# shield.net
KiCad netlist of a schematic drawn in EAGLE
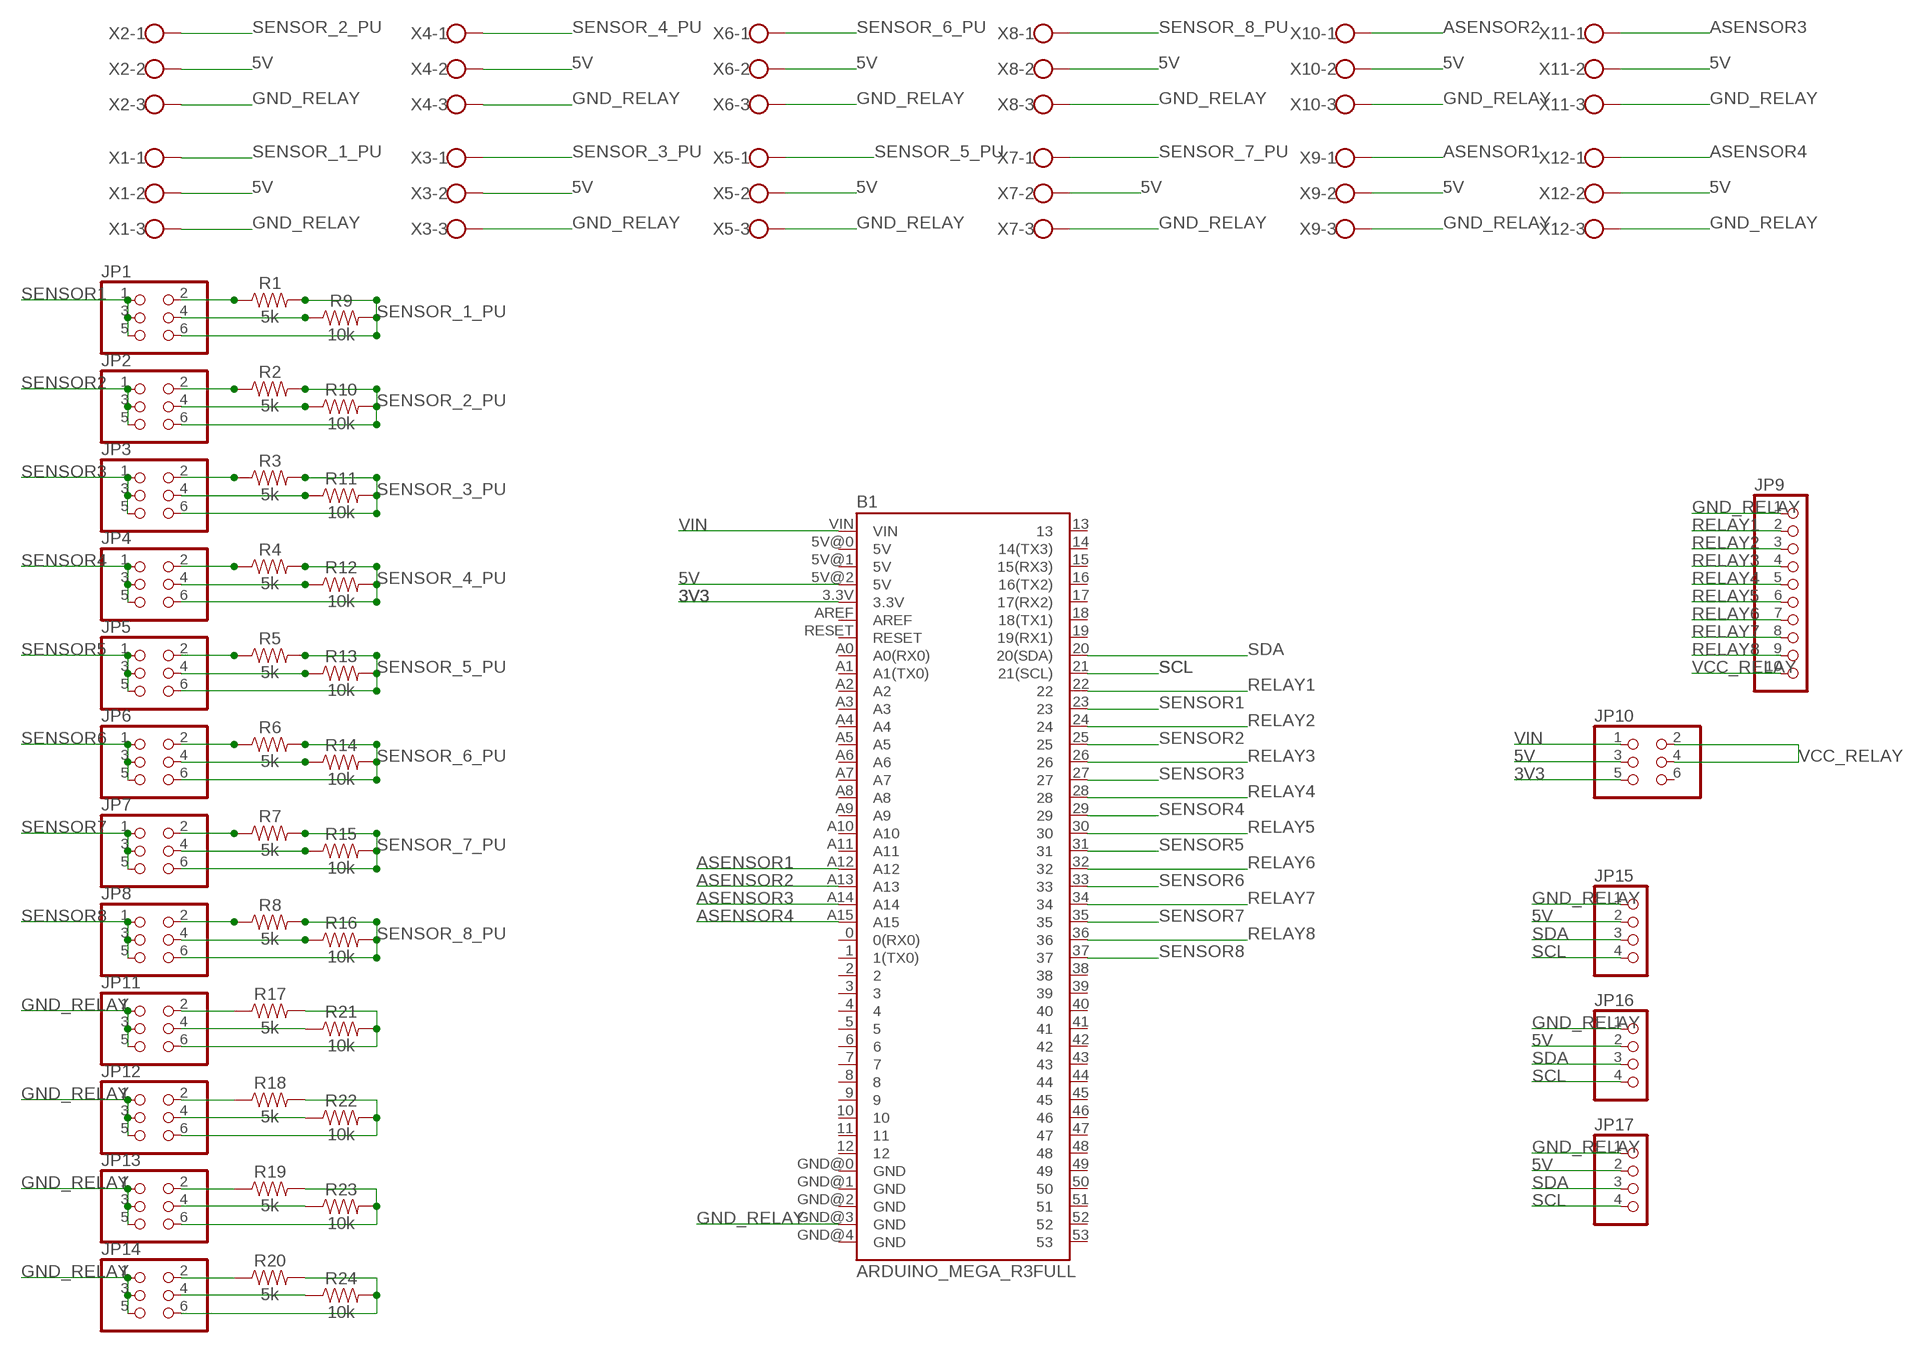
[diagram p0: schematic, sheet 1]

(export (version "E")
  (design (tool "Eeschema 10.0.6"))
  (components
    (comp (ref "B1")
      (value "ARDUINO_MEGA_R3FULL")
      (footprint "eagle-import:ARDUINO_MEGA")
      (libsource (lib "eagle-import") (part "ARDUINO_MEGA_R3FULL"))
    )
    (comp (ref "JP1")
      (value "PINHD-2X3")
      (footprint "eagle-import:2X03")
      (libsource (lib "eagle-import") (part "PINHD-2X3"))
    )
    (comp (ref "JP2")
      (value "PINHD-2X3")
      (footprint "eagle-import:2X03")
      (libsource (lib "eagle-import") (part "PINHD-2X3"))
    )
    (comp (ref "JP3")
      (value "PINHD-2X3")
      (footprint "eagle-import:2X03")
      (libsource (lib "eagle-import") (part "PINHD-2X3"))
    )
    (comp (ref "JP4")
      (value "PINHD-2X3")
      (footprint "eagle-import:2X03")
      (libsource (lib "eagle-import") (part "PINHD-2X3"))
    )
    (comp (ref "JP5")
      (value "PINHD-2X3")
      (footprint "eagle-import:2X03")
      (libsource (lib "eagle-import") (part "PINHD-2X3"))
    )
    (comp (ref "JP6")
      (value "PINHD-2X3")
      (footprint "eagle-import:2X03")
      (libsource (lib "eagle-import") (part "PINHD-2X3"))
    )
    (comp (ref "JP7")
      (value "PINHD-2X3")
      (footprint "eagle-import:2X03")
      (libsource (lib "eagle-import") (part "PINHD-2X3"))
    )
    (comp (ref "JP8")
      (value "PINHD-2X3")
      (footprint "eagle-import:2X03")
      (libsource (lib "eagle-import") (part "PINHD-2X3"))
    )
    (comp (ref "JP9")
      (value "PINHD-1X10")
      (footprint "eagle-import:1X10")
      (libsource (lib "eagle-import") (part "PINHD-1X10"))
    )
    (comp (ref "JP10")
      (value "PINHD-2X3")
      (footprint "eagle-import:2X03")
      (libsource (lib "eagle-import") (part "PINHD-2X3"))
    )
    (comp (ref "JP11")
      (value "PINHD-2X3")
      (footprint "eagle-import:2X03")
      (libsource (lib "eagle-import") (part "PINHD-2X3"))
    )
    (comp (ref "JP12")
      (value "PINHD-2X3")
      (footprint "eagle-import:2X03")
      (libsource (lib "eagle-import") (part "PINHD-2X3"))
    )
    (comp (ref "JP13")
      (value "PINHD-2X3")
      (footprint "eagle-import:2X03")
      (libsource (lib "eagle-import") (part "PINHD-2X3"))
    )
    (comp (ref "JP14")
      (value "PINHD-2X3")
      (footprint "eagle-import:2X03")
      (libsource (lib "eagle-import") (part "PINHD-2X3"))
    )
    (comp (ref "JP15")
      (value "PINHD-1X4")
      (footprint "eagle-import:1X04")
      (libsource (lib "eagle-import") (part "PINHD-1X4"))
    )
    (comp (ref "JP16")
      (value "PINHD-1X4")
      (footprint "eagle-import:1X04")
      (libsource (lib "eagle-import") (part "PINHD-1X4"))
    )
    (comp (ref "JP17")
      (value "PINHD-1X4")
      (footprint "eagle-import:1X04")
      (libsource (lib "eagle-import") (part "PINHD-1X4"))
    )
    (comp (ref "R1")
      (value "5k")
      (footprint "eagle-import:AXIAL-0.3")
      (libsource (lib "eagle-import") (part "10KOHM-HORIZ-1/4W-1%"))
    )
    (comp (ref "R2")
      (value "5k")
      (footprint "eagle-import:AXIAL-0.3")
      (libsource (lib "eagle-import") (part "10KOHM-HORIZ-1/4W-1%"))
    )
    (comp (ref "R3")
      (value "5k")
      (footprint "eagle-import:AXIAL-0.3")
      (libsource (lib "eagle-import") (part "10KOHM-HORIZ-1/4W-1%"))
    )
    (comp (ref "R4")
      (value "5k")
      (footprint "eagle-import:AXIAL-0.3")
      (libsource (lib "eagle-import") (part "10KOHM-HORIZ-1/4W-1%"))
    )
    (comp (ref "R5")
      (value "5k")
      (footprint "eagle-import:AXIAL-0.3")
      (libsource (lib "eagle-import") (part "10KOHM-HORIZ-1/4W-1%"))
    )
    (comp (ref "R6")
      (value "5k")
      (footprint "eagle-import:AXIAL-0.3")
      (libsource (lib "eagle-import") (part "10KOHM-HORIZ-1/4W-1%"))
    )
    (comp (ref "R7")
      (value "5k")
      (footprint "eagle-import:AXIAL-0.3")
      (libsource (lib "eagle-import") (part "10KOHM-HORIZ-1/4W-1%"))
    )
    (comp (ref "R8")
      (value "5k")
      (footprint "eagle-import:AXIAL-0.3")
      (libsource (lib "eagle-import") (part "10KOHM-HORIZ-1/4W-1%"))
    )
    (comp (ref "R9")
      (value "10k")
      (footprint "eagle-import:AXIAL-0.3")
      (libsource (lib "eagle-import") (part "10KOHM-HORIZ-1/4W-1%"))
    )
    (comp (ref "R10")
      (value "10k")
      (footprint "eagle-import:AXIAL-0.3")
      (libsource (lib "eagle-import") (part "10KOHM-HORIZ-1/4W-1%"))
    )
    (comp (ref "R11")
      (value "10k")
      (footprint "eagle-import:AXIAL-0.3")
      (libsource (lib "eagle-import") (part "10KOHM-HORIZ-1/4W-1%"))
    )
    (comp (ref "R12")
      (value "10k")
      (footprint "eagle-import:AXIAL-0.3")
      (libsource (lib "eagle-import") (part "10KOHM-HORIZ-1/4W-1%"))
    )
    (comp (ref "R13")
      (value "10k")
      (footprint "eagle-import:AXIAL-0.3")
      (libsource (lib "eagle-import") (part "10KOHM-HORIZ-1/4W-1%"))
    )
    (comp (ref "R14")
      (value "10k")
      (footprint "eagle-import:AXIAL-0.3")
      (libsource (lib "eagle-import") (part "10KOHM-HORIZ-1/4W-1%"))
    )
    (comp (ref "R15")
      (value "10k")
      (footprint "eagle-import:AXIAL-0.3")
      (libsource (lib "eagle-import") (part "10KOHM-HORIZ-1/4W-1%"))
    )
    (comp (ref "R16")
      (value "10k")
      (footprint "eagle-import:AXIAL-0.3")
      (libsource (lib "eagle-import") (part "10KOHM-HORIZ-1/4W-1%"))
    )
    (comp (ref "R17")
      (value "5k")
      (footprint "eagle-import:AXIAL-0.3")
      (libsource (lib "eagle-import") (part "10KOHM-HORIZ-1/4W-1%"))
    )
    (comp (ref "R18")
      (value "5k")
      (footprint "eagle-import:AXIAL-0.3")
      (libsource (lib "eagle-import") (part "10KOHM-HORIZ-1/4W-1%"))
    )
    (comp (ref "R19")
      (value "5k")
      (footprint "eagle-import:AXIAL-0.3")
      (libsource (lib "eagle-import") (part "10KOHM-HORIZ-1/4W-1%"))
    )
    (comp (ref "R20")
      (value "5k")
      (footprint "eagle-import:AXIAL-0.3")
      (libsource (lib "eagle-import") (part "10KOHM-HORIZ-1/4W-1%"))
    )
    (comp (ref "R21")
      (value "10k")
      (footprint "eagle-import:AXIAL-0.3")
      (libsource (lib "eagle-import") (part "10KOHM-HORIZ-1/4W-1%"))
    )
    (comp (ref "R22")
      (value "10k")
      (footprint "eagle-import:AXIAL-0.3")
      (libsource (lib "eagle-import") (part "10KOHM-HORIZ-1/4W-1%"))
    )
    (comp (ref "R23")
      (value "10k")
      (footprint "eagle-import:AXIAL-0.3")
      (libsource (lib "eagle-import") (part "10KOHM-HORIZ-1/4W-1%"))
    )
    (comp (ref "R24")
      (value "10k")
      (footprint "eagle-import:AXIAL-0.3")
      (libsource (lib "eagle-import") (part "10KOHM-HORIZ-1/4W-1%"))
    )
    (comp (ref "X1")
      (value "W237-103")
      (footprint "eagle-import:W237-103")
      (fields (field (name "MPN") "237-103"))
      (libsource (lib "eagle-import") (part "W237-103"))
    )
    (comp (ref "X2")
      (value "W237-103")
      (footprint "eagle-import:W237-103")
      (fields (field (name "MPN") "237-103"))
      (libsource (lib "eagle-import") (part "W237-103"))
    )
    (comp (ref "X3")
      (value "W237-103")
      (footprint "eagle-import:W237-103")
      (fields (field (name "MPN") "237-103"))
      (libsource (lib "eagle-import") (part "W237-103"))
    )
    (comp (ref "X4")
      (value "W237-103")
      (footprint "eagle-import:W237-103")
      (fields (field (name "MPN") "237-103"))
      (libsource (lib "eagle-import") (part "W237-103"))
    )
    (comp (ref "X5")
      (value "W237-103")
      (footprint "eagle-import:W237-103")
      (fields (field (name "MPN") "237-103"))
      (libsource (lib "eagle-import") (part "W237-103"))
    )
    (comp (ref "X6")
      (value "W237-103")
      (footprint "eagle-import:W237-103")
      (fields (field (name "MPN") "237-103"))
      (libsource (lib "eagle-import") (part "W237-103"))
    )
    (comp (ref "X7")
      (value "W237-103")
      (footprint "eagle-import:W237-103")
      (fields (field (name "MPN") "237-103"))
      (libsource (lib "eagle-import") (part "W237-103"))
    )
    (comp (ref "X8")
      (value "W237-103")
      (footprint "eagle-import:W237-103")
      (fields (field (name "MPN") "237-103"))
      (libsource (lib "eagle-import") (part "W237-103"))
    )
    (comp (ref "X9")
      (value "W237-103")
      (footprint "eagle-import:W237-103")
      (fields (field (name "MPN") "237-103"))
      (libsource (lib "eagle-import") (part "W237-103"))
    )
    (comp (ref "X10")
      (value "W237-103")
      (footprint "eagle-import:W237-103")
      (fields (field (name "MPN") "237-103"))
      (libsource (lib "eagle-import") (part "W237-103"))
    )
    (comp (ref "X11")
      (value "W237-103")
      (footprint "eagle-import:W237-103")
      (fields (field (name "MPN") "237-103"))
      (libsource (lib "eagle-import") (part "W237-103"))
    )
    (comp (ref "X12")
      (value "W237-103")
      (footprint "eagle-import:W237-103")
      (fields (field (name "MPN") "237-103"))
      (libsource (lib "eagle-import") (part "W237-103"))
    )
  )
  (nets
    (net (code "1") (name "/3V3") (class "Default")
      (node (ref "B1") (pin "3.3V") (pinfunction "3.3V_3.3V") (pintype "bidirectional"))
      (node (ref "JP10") (pin "5") (pinfunction "5_5") (pintype "passive"))
    )
    (net (code "2") (name "/5V") (class "Default")
      (node (ref "B1") (pin "5V@2") (pinfunction "5V_5V@2") (pintype "bidirectional"))
      (node (ref "JP10") (pin "3") (pinfunction "3_3") (pintype "passive"))
      (node (ref "JP15") (pin "2") (pinfunction "2_2") (pintype "passive"))
      (node (ref "JP16") (pin "2") (pinfunction "2_2") (pintype "passive"))
      (node (ref "JP17") (pin "2") (pinfunction "2_2") (pintype "passive"))
      (node (ref "X1") (pin "2") (pinfunction "KL_2") (pintype "passive"))
      (node (ref "X10") (pin "2") (pinfunction "KL_2") (pintype "passive"))
      (node (ref "X11") (pin "2") (pinfunction "KL_2") (pintype "passive"))
      (node (ref "X12") (pin "2") (pinfunction "KL_2") (pintype "passive"))
      (node (ref "X2") (pin "2") (pinfunction "KL_2") (pintype "passive"))
      (node (ref "X3") (pin "2") (pinfunction "KL_2") (pintype "passive"))
      (node (ref "X4") (pin "2") (pinfunction "KL_2") (pintype "passive"))
      (node (ref "X5") (pin "2") (pinfunction "KL_2") (pintype "passive"))
      (node (ref "X6") (pin "2") (pinfunction "KL_2") (pintype "passive"))
      (node (ref "X7") (pin "2") (pinfunction "KL_2") (pintype "passive"))
      (node (ref "X8") (pin "2") (pinfunction "KL_2") (pintype "passive"))
      (node (ref "X9") (pin "2") (pinfunction "KL_2") (pintype "passive"))
    )
    (net (code "3") (name "/ASENSOR1") (class "Default")
      (node (ref "B1") (pin "A12") (pinfunction "A12_A12") (pintype "bidirectional"))
      (node (ref "X9") (pin "1") (pinfunction "KL_1") (pintype "passive"))
    )
    (net (code "4") (name "/ASENSOR2") (class "Default")
      (node (ref "B1") (pin "A13") (pinfunction "A13_A13") (pintype "bidirectional"))
      (node (ref "X10") (pin "1") (pinfunction "KL_1") (pintype "passive"))
    )
    (net (code "5") (name "/ASENSOR3") (class "Default")
      (node (ref "B1") (pin "A14") (pinfunction "A14_A14") (pintype "bidirectional"))
      (node (ref "X11") (pin "1") (pinfunction "KL_1") (pintype "passive"))
    )
    (net (code "6") (name "/ASENSOR4") (class "Default")
      (node (ref "B1") (pin "A15") (pinfunction "A15_A15") (pintype "bidirectional"))
      (node (ref "X12") (pin "1") (pinfunction "KL_1") (pintype "passive"))
    )
    (net (code "7") (name "/GND_RELAY") (class "Default")
      (node (ref "B1") (pin "GND@3") (pinfunction "GND_GND@3") (pintype "bidirectional"))
      (node (ref "JP11") (pin "1") (pinfunction "1_1") (pintype "passive"))
      (node (ref "JP11") (pin "3") (pinfunction "3_3") (pintype "passive"))
      (node (ref "JP11") (pin "5") (pinfunction "5_5") (pintype "passive"))
      (node (ref "JP12") (pin "1") (pinfunction "1_1") (pintype "passive"))
      (node (ref "JP12") (pin "3") (pinfunction "3_3") (pintype "passive"))
      (node (ref "JP12") (pin "5") (pinfunction "5_5") (pintype "passive"))
      (node (ref "JP13") (pin "1") (pinfunction "1_1") (pintype "passive"))
      (node (ref "JP13") (pin "3") (pinfunction "3_3") (pintype "passive"))
      (node (ref "JP13") (pin "5") (pinfunction "5_5") (pintype "passive"))
      (node (ref "JP14") (pin "1") (pinfunction "1_1") (pintype "passive"))
      (node (ref "JP14") (pin "3") (pinfunction "3_3") (pintype "passive"))
      (node (ref "JP14") (pin "5") (pinfunction "5_5") (pintype "passive"))
      (node (ref "JP15") (pin "1") (pinfunction "1_1") (pintype "passive"))
      (node (ref "JP16") (pin "1") (pinfunction "1_1") (pintype "passive"))
      (node (ref "JP17") (pin "1") (pinfunction "1_1") (pintype "passive"))
      (node (ref "JP9") (pin "1") (pinfunction "1_1") (pintype "passive"))
      (node (ref "X1") (pin "3") (pinfunction "KL_3") (pintype "passive"))
      (node (ref "X10") (pin "3") (pinfunction "KL_3") (pintype "passive"))
      (node (ref "X11") (pin "3") (pinfunction "KL_3") (pintype "passive"))
      (node (ref "X12") (pin "3") (pinfunction "KL_3") (pintype "passive"))
      (node (ref "X2") (pin "3") (pinfunction "KL_3") (pintype "passive"))
      (node (ref "X3") (pin "3") (pinfunction "KL_3") (pintype "passive"))
      (node (ref "X4") (pin "3") (pinfunction "KL_3") (pintype "passive"))
      (node (ref "X5") (pin "3") (pinfunction "KL_3") (pintype "passive"))
      (node (ref "X6") (pin "3") (pinfunction "KL_3") (pintype "passive"))
      (node (ref "X7") (pin "3") (pinfunction "KL_3") (pintype "passive"))
      (node (ref "X8") (pin "3") (pinfunction "KL_3") (pintype "passive"))
      (node (ref "X9") (pin "3") (pinfunction "KL_3") (pintype "passive"))
    )
    (net (code "8") (name "/RELAY1") (class "Default")
      (node (ref "B1") (pin "22") (pinfunction "22_22") (pintype "bidirectional"))
      (node (ref "JP9") (pin "2") (pinfunction "2_2") (pintype "passive"))
    )
    (net (code "9") (name "/RELAY2") (class "Default")
      (node (ref "B1") (pin "24") (pinfunction "24_24") (pintype "bidirectional"))
      (node (ref "JP9") (pin "3") (pinfunction "3_3") (pintype "passive"))
    )
    (net (code "10") (name "/RELAY3") (class "Default")
      (node (ref "B1") (pin "26") (pinfunction "26_26") (pintype "bidirectional"))
      (node (ref "JP9") (pin "4") (pinfunction "4_4") (pintype "passive"))
    )
    (net (code "11") (name "/RELAY4") (class "Default")
      (node (ref "B1") (pin "28") (pinfunction "28_28") (pintype "bidirectional"))
      (node (ref "JP9") (pin "5") (pinfunction "5_5") (pintype "passive"))
    )
    (net (code "12") (name "/RELAY5") (class "Default")
      (node (ref "B1") (pin "30") (pinfunction "30_30") (pintype "bidirectional"))
      (node (ref "JP9") (pin "6") (pinfunction "6_6") (pintype "passive"))
    )
    (net (code "13") (name "/RELAY6") (class "Default")
      (node (ref "B1") (pin "32") (pinfunction "32_32") (pintype "bidirectional"))
      (node (ref "JP9") (pin "7") (pinfunction "7_7") (pintype "passive"))
    )
    (net (code "14") (name "/RELAY7") (class "Default")
      (node (ref "B1") (pin "34") (pinfunction "34_34") (pintype "bidirectional"))
      (node (ref "JP9") (pin "8") (pinfunction "8_8") (pintype "passive"))
    )
    (net (code "15") (name "/RELAY8") (class "Default")
      (node (ref "B1") (pin "36") (pinfunction "36_36") (pintype "bidirectional"))
      (node (ref "JP9") (pin "9") (pinfunction "9_9") (pintype "passive"))
    )
    (net (code "16") (name "/SCL") (class "Default")
      (node (ref "B1") (pin "21") (pinfunction "21(SCL)_21") (pintype "bidirectional"))
      (node (ref "JP15") (pin "4") (pinfunction "4_4") (pintype "passive"))
      (node (ref "JP16") (pin "4") (pinfunction "4_4") (pintype "passive"))
      (node (ref "JP17") (pin "4") (pinfunction "4_4") (pintype "passive"))
    )
    (net (code "17") (name "/SDA") (class "Default")
      (node (ref "B1") (pin "20") (pinfunction "20(SDA)_20") (pintype "bidirectional"))
      (node (ref "JP15") (pin "3") (pinfunction "3_3") (pintype "passive"))
      (node (ref "JP16") (pin "3") (pinfunction "3_3") (pintype "passive"))
      (node (ref "JP17") (pin "3") (pinfunction "3_3") (pintype "passive"))
    )
    (net (code "18") (name "/SENSOR1") (class "Default")
      (node (ref "B1") (pin "23") (pinfunction "23_23") (pintype "bidirectional"))
      (node (ref "JP1") (pin "1") (pinfunction "1_1") (pintype "passive"))
      (node (ref "JP1") (pin "3") (pinfunction "3_3") (pintype "passive"))
      (node (ref "JP1") (pin "5") (pinfunction "5_5") (pintype "passive"))
    )
    (net (code "19") (name "/SENSOR2") (class "Default")
      (node (ref "B1") (pin "25") (pinfunction "25_25") (pintype "bidirectional"))
      (node (ref "JP2") (pin "1") (pinfunction "1_1") (pintype "passive"))
      (node (ref "JP2") (pin "3") (pinfunction "3_3") (pintype "passive"))
      (node (ref "JP2") (pin "5") (pinfunction "5_5") (pintype "passive"))
    )
    (net (code "20") (name "/SENSOR3") (class "Default")
      (node (ref "B1") (pin "27") (pinfunction "27_27") (pintype "bidirectional"))
      (node (ref "JP3") (pin "1") (pinfunction "1_1") (pintype "passive"))
      (node (ref "JP3") (pin "3") (pinfunction "3_3") (pintype "passive"))
      (node (ref "JP3") (pin "5") (pinfunction "5_5") (pintype "passive"))
    )
    (net (code "21") (name "/SENSOR4") (class "Default")
      (node (ref "B1") (pin "29") (pinfunction "29_29") (pintype "bidirectional"))
      (node (ref "JP4") (pin "1") (pinfunction "1_1") (pintype "passive"))
      (node (ref "JP4") (pin "3") (pinfunction "3_3") (pintype "passive"))
      (node (ref "JP4") (pin "5") (pinfunction "5_5") (pintype "passive"))
    )
    (net (code "22") (name "/SENSOR5") (class "Default")
      (node (ref "B1") (pin "31") (pinfunction "31_31") (pintype "bidirectional"))
      (node (ref "JP5") (pin "1") (pinfunction "1_1") (pintype "passive"))
      (node (ref "JP5") (pin "3") (pinfunction "3_3") (pintype "passive"))
      (node (ref "JP5") (pin "5") (pinfunction "5_5") (pintype "passive"))
    )
    (net (code "23") (name "/SENSOR6") (class "Default")
      (node (ref "B1") (pin "33") (pinfunction "33_33") (pintype "bidirectional"))
      (node (ref "JP6") (pin "1") (pinfunction "1_1") (pintype "passive"))
      (node (ref "JP6") (pin "3") (pinfunction "3_3") (pintype "passive"))
      (node (ref "JP6") (pin "5") (pinfunction "5_5") (pintype "passive"))
    )
    (net (code "24") (name "/SENSOR7") (class "Default")
      (node (ref "B1") (pin "35") (pinfunction "35_35") (pintype "bidirectional"))
      (node (ref "JP7") (pin "1") (pinfunction "1_1") (pintype "passive"))
      (node (ref "JP7") (pin "3") (pinfunction "3_3") (pintype "passive"))
      (node (ref "JP7") (pin "5") (pinfunction "5_5") (pintype "passive"))
    )
    (net (code "25") (name "/SENSOR8") (class "Default")
      (node (ref "B1") (pin "37") (pinfunction "37_37") (pintype "bidirectional"))
      (node (ref "JP8") (pin "1") (pinfunction "1_1") (pintype "passive"))
      (node (ref "JP8") (pin "3") (pinfunction "3_3") (pintype "passive"))
      (node (ref "JP8") (pin "5") (pinfunction "5_5") (pintype "passive"))
    )
    (net (code "26") (name "/SENSOR_1_PU") (class "Default")
      (node (ref "JP1") (pin "6") (pinfunction "6_6") (pintype "passive"))
      (node (ref "R1") (pin "P$2") (pinfunction "2_P$2") (pintype "passive"))
      (node (ref "R9") (pin "P$2") (pinfunction "2_P$2") (pintype "passive"))
      (node (ref "X1") (pin "1") (pinfunction "KL_1") (pintype "passive"))
    )
    (net (code "27") (name "/SENSOR_2_PU") (class "Default")
      (node (ref "JP2") (pin "6") (pinfunction "6_6") (pintype "passive"))
      (node (ref "R10") (pin "P$2") (pinfunction "2_P$2") (pintype "passive"))
      (node (ref "R2") (pin "P$2") (pinfunction "2_P$2") (pintype "passive"))
      (node (ref "X2") (pin "1") (pinfunction "KL_1") (pintype "passive"))
    )
    (net (code "28") (name "/SENSOR_3_PU") (class "Default")
      (node (ref "JP3") (pin "6") (pinfunction "6_6") (pintype "passive"))
      (node (ref "R11") (pin "P$2") (pinfunction "2_P$2") (pintype "passive"))
      (node (ref "R3") (pin "P$2") (pinfunction "2_P$2") (pintype "passive"))
      (node (ref "X3") (pin "1") (pinfunction "KL_1") (pintype "passive"))
    )
    (net (code "29") (name "/SENSOR_4_PU") (class "Default")
      (node (ref "JP4") (pin "6") (pinfunction "6_6") (pintype "passive"))
      (node (ref "R12") (pin "P$2") (pinfunction "2_P$2") (pintype "passive"))
      (node (ref "R4") (pin "P$2") (pinfunction "2_P$2") (pintype "passive"))
      (node (ref "X4") (pin "1") (pinfunction "KL_1") (pintype "passive"))
    )
    (net (code "30") (name "/SENSOR_5_PU") (class "Default")
      (node (ref "JP5") (pin "6") (pinfunction "6_6") (pintype "passive"))
      (node (ref "R13") (pin "P$2") (pinfunction "2_P$2") (pintype "passive"))
      (node (ref "R5") (pin "P$2") (pinfunction "2_P$2") (pintype "passive"))
      (node (ref "X5") (pin "1") (pinfunction "KL_1") (pintype "passive"))
    )
    (net (code "31") (name "/SENSOR_6_PU") (class "Default")
      (node (ref "JP6") (pin "6") (pinfunction "6_6") (pintype "passive"))
      (node (ref "R14") (pin "P$2") (pinfunction "2_P$2") (pintype "passive"))
      (node (ref "R6") (pin "P$2") (pinfunction "2_P$2") (pintype "passive"))
      (node (ref "X6") (pin "1") (pinfunction "KL_1") (pintype "passive"))
    )
    (net (code "32") (name "/SENSOR_7_PU") (class "Default")
      (node (ref "JP7") (pin "6") (pinfunction "6_6") (pintype "passive"))
      (node (ref "R15") (pin "P$2") (pinfunction "2_P$2") (pintype "passive"))
      (node (ref "R7") (pin "P$2") (pinfunction "2_P$2") (pintype "passive"))
      (node (ref "X7") (pin "1") (pinfunction "KL_1") (pintype "passive"))
    )
    (net (code "33") (name "/SENSOR_8_PU") (class "Default")
      (node (ref "JP8") (pin "6") (pinfunction "6_6") (pintype "passive"))
      (node (ref "R16") (pin "P$2") (pinfunction "2_P$2") (pintype "passive"))
      (node (ref "R8") (pin "P$2") (pinfunction "2_P$2") (pintype "passive"))
      (node (ref "X8") (pin "1") (pinfunction "KL_1") (pintype "passive"))
    )
    (net (code "34") (name "/VCC_RELAY") (class "Default")
      (node (ref "JP10") (pin "2") (pinfunction "2_2") (pintype "passive"))
      (node (ref "JP10") (pin "4") (pinfunction "4_4") (pintype "passive"))
      (node (ref "JP9") (pin "10") (pinfunction "10_10") (pintype "passive"))
    )
    (net (code "35") (name "/VIN") (class "Default")
      (node (ref "B1") (pin "VIN") (pinfunction "VIN_VIN") (pintype "bidirectional"))
      (node (ref "JP10") (pin "1") (pinfunction "1_1") (pintype "passive"))
    )
    (net (code "36") (name "Net-(R1-1)") (class "Default")
      (node (ref "JP1") (pin "2") (pinfunction "2_2") (pintype "passive"))
      (node (ref "R1") (pin "P$1") (pinfunction "1_P$1") (pintype "passive"))
    )
    (net (code "37") (name "Net-(R2-1)") (class "Default")
      (node (ref "JP2") (pin "2") (pinfunction "2_2") (pintype "passive"))
      (node (ref "R2") (pin "P$1") (pinfunction "1_P$1") (pintype "passive"))
    )
    (net (code "38") (name "Net-(R3-1)") (class "Default")
      (node (ref "JP3") (pin "2") (pinfunction "2_2") (pintype "passive"))
      (node (ref "R3") (pin "P$1") (pinfunction "1_P$1") (pintype "passive"))
    )
    (net (code "39") (name "Net-(R4-1)") (class "Default")
      (node (ref "JP4") (pin "2") (pinfunction "2_2") (pintype "passive"))
      (node (ref "R4") (pin "P$1") (pinfunction "1_P$1") (pintype "passive"))
    )
    (net (code "40") (name "Net-(R5-1)") (class "Default")
      (node (ref "JP5") (pin "2") (pinfunction "2_2") (pintype "passive"))
      (node (ref "R5") (pin "P$1") (pinfunction "1_P$1") (pintype "passive"))
    )
    (net (code "41") (name "Net-(R6-1)") (class "Default")
      (node (ref "JP6") (pin "2") (pinfunction "2_2") (pintype "passive"))
      (node (ref "R6") (pin "P$1") (pinfunction "1_P$1") (pintype "passive"))
    )
    (net (code "42") (name "Net-(R7-1)") (class "Default")
      (node (ref "JP7") (pin "2") (pinfunction "2_2") (pintype "passive"))
      (node (ref "R7") (pin "P$1") (pinfunction "1_P$1") (pintype "passive"))
    )
    (net (code "43") (name "Net-(R8-1)") (class "Default")
      (node (ref "JP8") (pin "2") (pinfunction "2_2") (pintype "passive"))
      (node (ref "R8") (pin "P$1") (pinfunction "1_P$1") (pintype "passive"))
    )
    (net (code "44") (name "Net-(R9-1)") (class "Default")
      (node (ref "JP1") (pin "4") (pinfunction "4_4") (pintype "passive"))
      (node (ref "R9") (pin "P$1") (pinfunction "1_P$1") (pintype "passive"))
    )
    (net (code "45") (name "Net-(R10-1)") (class "Default")
      (node (ref "JP2") (pin "4") (pinfunction "4_4") (pintype "passive"))
      (node (ref "R10") (pin "P$1") (pinfunction "1_P$1") (pintype "passive"))
    )
    (net (code "46") (name "Net-(R11-1)") (class "Default")
      (node (ref "JP3") (pin "4") (pinfunction "4_4") (pintype "passive"))
      (node (ref "R11") (pin "P$1") (pinfunction "1_P$1") (pintype "passive"))
    )
    (net (code "47") (name "Net-(R12-1)") (class "Default")
      (node (ref "JP4") (pin "4") (pinfunction "4_4") (pintype "passive"))
      (node (ref "R12") (pin "P$1") (pinfunction "1_P$1") (pintype "passive"))
    )
    (net (code "48") (name "Net-(R13-1)") (class "Default")
      (node (ref "JP5") (pin "4") (pinfunction "4_4") (pintype "passive"))
      (node (ref "R13") (pin "P$1") (pinfunction "1_P$1") (pintype "passive"))
    )
    (net (code "49") (name "Net-(R14-1)") (class "Default")
      (node (ref "JP6") (pin "4") (pinfunction "4_4") (pintype "passive"))
      (node (ref "R14") (pin "P$1") (pinfunction "1_P$1") (pintype "passive"))
    )
    (net (code "50") (name "Net-(R15-1)") (class "Default")
      (node (ref "JP7") (pin "4") (pinfunction "4_4") (pintype "passive"))
      (node (ref "R15") (pin "P$1") (pinfunction "1_P$1") (pintype "passive"))
    )
    (net (code "51") (name "Net-(R16-1)") (class "Default")
      (node (ref "JP8") (pin "4") (pinfunction "4_4") (pintype "passive"))
      (node (ref "R16") (pin "P$1") (pinfunction "1_P$1") (pintype "passive"))
    )
    (net (code "52") (name "Net-(R17-1)") (class "Default")
      (node (ref "JP11") (pin "2") (pinfunction "2_2") (pintype "passive"))
      (node (ref "R17") (pin "P$1") (pinfunction "1_P$1") (pintype "passive"))
    )
    (net (code "53") (name "Net-(R17-2)") (class "Default")
      (node (ref "JP11") (pin "6") (pinfunction "6_6") (pintype "passive"))
      (node (ref "R17") (pin "P$2") (pinfunction "2_P$2") (pintype "passive"))
      (node (ref "R21") (pin "P$2") (pinfunction "2_P$2") (pintype "passive"))
    )
    (net (code "54") (name "Net-(R18-1)") (class "Default")
      (node (ref "JP12") (pin "2") (pinfunction "2_2") (pintype "passive"))
      (node (ref "R18") (pin "P$1") (pinfunction "1_P$1") (pintype "passive"))
    )
    (net (code "55") (name "Net-(R18-2)") (class "Default")
      (node (ref "JP12") (pin "6") (pinfunction "6_6") (pintype "passive"))
      (node (ref "R18") (pin "P$2") (pinfunction "2_P$2") (pintype "passive"))
      (node (ref "R22") (pin "P$2") (pinfunction "2_P$2") (pintype "passive"))
    )
    (net (code "56") (name "Net-(R19-1)") (class "Default")
      (node (ref "JP13") (pin "2") (pinfunction "2_2") (pintype "passive"))
      (node (ref "R19") (pin "P$1") (pinfunction "1_P$1") (pintype "passive"))
    )
    (net (code "57") (name "Net-(R19-2)") (class "Default")
      (node (ref "JP13") (pin "6") (pinfunction "6_6") (pintype "passive"))
      (node (ref "R19") (pin "P$2") (pinfunction "2_P$2") (pintype "passive"))
      (node (ref "R23") (pin "P$2") (pinfunction "2_P$2") (pintype "passive"))
    )
    (net (code "58") (name "Net-(R20-1)") (class "Default")
      (node (ref "JP14") (pin "2") (pinfunction "2_2") (pintype "passive"))
      (node (ref "R20") (pin "P$1") (pinfunction "1_P$1") (pintype "passive"))
    )
    (net (code "59") (name "Net-(R20-2)") (class "Default")
      (node (ref "JP14") (pin "6") (pinfunction "6_6") (pintype "passive"))
      (node (ref "R20") (pin "P$2") (pinfunction "2_P$2") (pintype "passive"))
      (node (ref "R24") (pin "P$2") (pinfunction "2_P$2") (pintype "passive"))
    )
    (net (code "60") (name "Net-(R21-1)") (class "Default")
      (node (ref "JP11") (pin "4") (pinfunction "4_4") (pintype "passive"))
      (node (ref "R21") (pin "P$1") (pinfunction "1_P$1") (pintype "passive"))
    )
    (net (code "61") (name "Net-(R22-1)") (class "Default")
      (node (ref "JP12") (pin "4") (pinfunction "4_4") (pintype "passive"))
      (node (ref "R22") (pin "P$1") (pinfunction "1_P$1") (pintype "passive"))
    )
    (net (code "62") (name "Net-(R23-1)") (class "Default")
      (node (ref "JP13") (pin "4") (pinfunction "4_4") (pintype "passive"))
      (node (ref "R23") (pin "P$1") (pinfunction "1_P$1") (pintype "passive"))
    )
    (net (code "63") (name "Net-(R24-1)") (class "Default")
      (node (ref "JP14") (pin "4") (pinfunction "4_4") (pintype "passive"))
      (node (ref "R24") (pin "P$1") (pinfunction "1_P$1") (pintype "passive"))
    )
    (net (code "64") (name "unconnected-(B1-0(RX0)-Pad0)") (class "Default")
      (node (ref "B1") (pin "0") (pinfunction "0(RX0)_0") (pintype "bidirectional"))
    )
    (net (code "65") (name "unconnected-(B1-1(TX0)-Pad1)") (class "Default")
      (node (ref "B1") (pin "1") (pinfunction "1(TX0)_1") (pintype "bidirectional"))
    )
    (net (code "66") (name "unconnected-(B1-5V-Pad5V@0)") (class "Default")
      (node (ref "B1") (pin "5V@0") (pinfunction "5V_5V@0") (pintype "bidirectional"))
    )
    (net (code "67") (name "unconnected-(B1-5V-Pad5V@1)") (class "Default")
      (node (ref "B1") (pin "5V@1") (pinfunction "5V_5V@1") (pintype "bidirectional"))
    )
    (net (code "68") (name "unconnected-(B1-14(TX3)-Pad14)") (class "Default")
      (node (ref "B1") (pin "14") (pinfunction "14(TX3)_14") (pintype "bidirectional"))
    )
    (net (code "69") (name "unconnected-(B1-15(RX3)-Pad15)") (class "Default")
      (node (ref "B1") (pin "15") (pinfunction "15(RX3)_15") (pintype "bidirectional"))
    )
    (net (code "70") (name "unconnected-(B1-16(TX2)-Pad16)") (class "Default")
      (node (ref "B1") (pin "16") (pinfunction "16(TX2)_16") (pintype "bidirectional"))
    )
    (net (code "71") (name "unconnected-(B1-17(RX2)-Pad17)") (class "Default")
      (node (ref "B1") (pin "17") (pinfunction "17(RX2)_17") (pintype "bidirectional"))
    )
    (net (code "72") (name "unconnected-(B1-18(TX1)-Pad18)") (class "Default")
      (node (ref "B1") (pin "18") (pinfunction "18(TX1)_18") (pintype "bidirectional"))
    )
    (net (code "73") (name "unconnected-(B1-19(RX1)-Pad19)") (class "Default")
      (node (ref "B1") (pin "19") (pinfunction "19(RX1)_19") (pintype "bidirectional"))
    )
    (net (code "74") (name "unconnected-(B1-A0(RX0)-PadA0)") (class "Default")
      (node (ref "B1") (pin "A0") (pinfunction "A0(RX0)_A0") (pintype "bidirectional"))
    )
    (net (code "75") (name "unconnected-(B1-A1(TX0)-PadA1)") (class "Default")
      (node (ref "B1") (pin "A1") (pinfunction "A1(TX0)_A1") (pintype "bidirectional"))
    )
    (net (code "76") (name "unconnected-(B1-GND-PadGND@0)") (class "Default")
      (node (ref "B1") (pin "GND@0") (pinfunction "GND_GND@0") (pintype "bidirectional"))
    )
    (net (code "77") (name "unconnected-(B1-GND-PadGND@1)") (class "Default")
      (node (ref "B1") (pin "GND@1") (pinfunction "GND_GND@1") (pintype "bidirectional"))
    )
    (net (code "78") (name "unconnected-(B1-GND-PadGND@2)") (class "Default")
      (node (ref "B1") (pin "GND@2") (pinfunction "GND_GND@2") (pintype "bidirectional"))
    )
    (net (code "79") (name "unconnected-(B1-GND-PadGND@4)") (class "Default")
      (node (ref "B1") (pin "GND@4") (pinfunction "GND_GND@4") (pintype "bidirectional"))
    )
    (net (code "80") (name "unconnected-(B1-Pad2)") (class "Default")
      (node (ref "B1") (pin "2") (pinfunction "2_2") (pintype "bidirectional"))
    )
    (net (code "81") (name "unconnected-(B1-Pad3)") (class "Default")
      (node (ref "B1") (pin "3") (pinfunction "3_3") (pintype "bidirectional"))
    )
    (net (code "82") (name "unconnected-(B1-Pad4)") (class "Default")
      (node (ref "B1") (pin "4") (pinfunction "4_4") (pintype "bidirectional"))
    )
    (net (code "83") (name "unconnected-(B1-Pad5)") (class "Default")
      (node (ref "B1") (pin "5") (pinfunction "5_5") (pintype "bidirectional"))
    )
    (net (code "84") (name "unconnected-(B1-Pad6)") (class "Default")
      (node (ref "B1") (pin "6") (pinfunction "6_6") (pintype "bidirectional"))
    )
    (net (code "85") (name "unconnected-(B1-Pad7)") (class "Default")
      (node (ref "B1") (pin "7") (pinfunction "7_7") (pintype "bidirectional"))
    )
    (net (code "86") (name "unconnected-(B1-Pad8)") (class "Default")
      (node (ref "B1") (pin "8") (pinfunction "8_8") (pintype "bidirectional"))
    )
    (net (code "87") (name "unconnected-(B1-Pad9)") (class "Default")
      (node (ref "B1") (pin "9") (pinfunction "9_9") (pintype "bidirectional"))
    )
    (net (code "88") (name "unconnected-(B1-Pad10)") (class "Default")
      (node (ref "B1") (pin "10") (pinfunction "10_10") (pintype "bidirectional"))
    )
    (net (code "89") (name "unconnected-(B1-Pad11)") (class "Default")
      (node (ref "B1") (pin "11") (pinfunction "11_11") (pintype "bidirectional"))
    )
    (net (code "90") (name "unconnected-(B1-Pad12)") (class "Default")
      (node (ref "B1") (pin "12") (pinfunction "12_12") (pintype "bidirectional"))
    )
    (net (code "91") (name "unconnected-(B1-Pad13)") (class "Default")
      (node (ref "B1") (pin "13") (pinfunction "13_13") (pintype "bidirectional"))
    )
    (net (code "92") (name "unconnected-(B1-Pad38)") (class "Default")
      (node (ref "B1") (pin "38") (pinfunction "38_38") (pintype "bidirectional"))
    )
    (net (code "93") (name "unconnected-(B1-Pad39)") (class "Default")
      (node (ref "B1") (pin "39") (pinfunction "39_39") (pintype "bidirectional"))
    )
    (net (code "94") (name "unconnected-(B1-Pad40)") (class "Default")
      (node (ref "B1") (pin "40") (pinfunction "40_40") (pintype "bidirectional"))
    )
    (net (code "95") (name "unconnected-(B1-Pad41)") (class "Default")
      (node (ref "B1") (pin "41") (pinfunction "41_41") (pintype "bidirectional"))
    )
    (net (code "96") (name "unconnected-(B1-Pad42)") (class "Default")
      (node (ref "B1") (pin "42") (pinfunction "42_42") (pintype "bidirectional"))
    )
    (net (code "97") (name "unconnected-(B1-Pad43)") (class "Default")
      (node (ref "B1") (pin "43") (pinfunction "43_43") (pintype "bidirectional"))
    )
    (net (code "98") (name "unconnected-(B1-Pad44)") (class "Default")
      (node (ref "B1") (pin "44") (pinfunction "44_44") (pintype "bidirectional"))
    )
    (net (code "99") (name "unconnected-(B1-Pad45)") (class "Default")
      (node (ref "B1") (pin "45") (pinfunction "45_45") (pintype "bidirectional"))
    )
    (net (code "100") (name "unconnected-(B1-Pad46)") (class "Default")
      (node (ref "B1") (pin "46") (pinfunction "46_46") (pintype "bidirectional"))
    )
    (net (code "101") (name "unconnected-(B1-Pad47)") (class "Default")
      (node (ref "B1") (pin "47") (pinfunction "47_47") (pintype "bidirectional"))
    )
    (net (code "102") (name "unconnected-(B1-Pad48)") (class "Default")
      (node (ref "B1") (pin "48") (pinfunction "48_48") (pintype "bidirectional"))
    )
    (net (code "103") (name "unconnected-(B1-Pad49)") (class "Default")
      (node (ref "B1") (pin "49") (pinfunction "49_49") (pintype "bidirectional"))
    )
    (net (code "104") (name "unconnected-(B1-Pad50)") (class "Default")
      (node (ref "B1") (pin "50") (pinfunction "50_50") (pintype "bidirectional"))
    )
    (net (code "105") (name "unconnected-(B1-Pad51)") (class "Default")
      (node (ref "B1") (pin "51") (pinfunction "51_51") (pintype "bidirectional"))
    )
    (net (code "106") (name "unconnected-(B1-Pad52)") (class "Default")
      (node (ref "B1") (pin "52") (pinfunction "52_52") (pintype "bidirectional"))
    )
    (net (code "107") (name "unconnected-(B1-Pad53)") (class "Default")
      (node (ref "B1") (pin "53") (pinfunction "53_53") (pintype "bidirectional"))
    )
    (net (code "108") (name "unconnected-(B1-PadA2)") (class "Default")
      (node (ref "B1") (pin "A2") (pinfunction "A2_A2") (pintype "bidirectional"))
    )
    (net (code "109") (name "unconnected-(B1-PadA3)") (class "Default")
      (node (ref "B1") (pin "A3") (pinfunction "A3_A3") (pintype "bidirectional"))
    )
    (net (code "110") (name "unconnected-(B1-PadA4)") (class "Default")
      (node (ref "B1") (pin "A4") (pinfunction "A4_A4") (pintype "bidirectional"))
    )
    (net (code "111") (name "unconnected-(B1-PadA5)") (class "Default")
      (node (ref "B1") (pin "A5") (pinfunction "A5_A5") (pintype "bidirectional"))
    )
    (net (code "112") (name "unconnected-(B1-PadA6)") (class "Default")
      (node (ref "B1") (pin "A6") (pinfunction "A6_A6") (pintype "bidirectional"))
    )
    (net (code "113") (name "unconnected-(B1-PadA7)") (class "Default")
      (node (ref "B1") (pin "A7") (pinfunction "A7_A7") (pintype "bidirectional"))
    )
    (net (code "114") (name "unconnected-(B1-PadA8)") (class "Default")
      (node (ref "B1") (pin "A8") (pinfunction "A8_A8") (pintype "bidirectional"))
    )
    (net (code "115") (name "unconnected-(B1-PadA9)") (class "Default")
      (node (ref "B1") (pin "A9") (pinfunction "A9_A9") (pintype "bidirectional"))
    )
    (net (code "116") (name "unconnected-(B1-PadA10)") (class "Default")
      (node (ref "B1") (pin "A10") (pinfunction "A10_A10") (pintype "bidirectional"))
    )
    (net (code "117") (name "unconnected-(B1-PadA11)") (class "Default")
      (node (ref "B1") (pin "A11") (pinfunction "A11_A11") (pintype "bidirectional"))
    )
    (net (code "118") (name "unconnected-(B1-PadAREF)") (class "Default")
      (node (ref "B1") (pin "AREF") (pinfunction "AREF_AREF") (pintype "bidirectional"))
    )
    (net (code "119") (name "unconnected-(B1-PadRESET)") (class "Default")
      (node (ref "B1") (pin "RESET") (pinfunction "RESET_RESET") (pintype "bidirectional"))
    )
    (net (code "120") (name "unconnected-(JP10-Pad6)") (class "Default")
      (node (ref "JP10") (pin "6") (pinfunction "6_6") (pintype "passive"))
    )
  )
)
